# dual_seq_v1_0_0_main.net
KiCad netlist of a schematic drawn in EAGLE
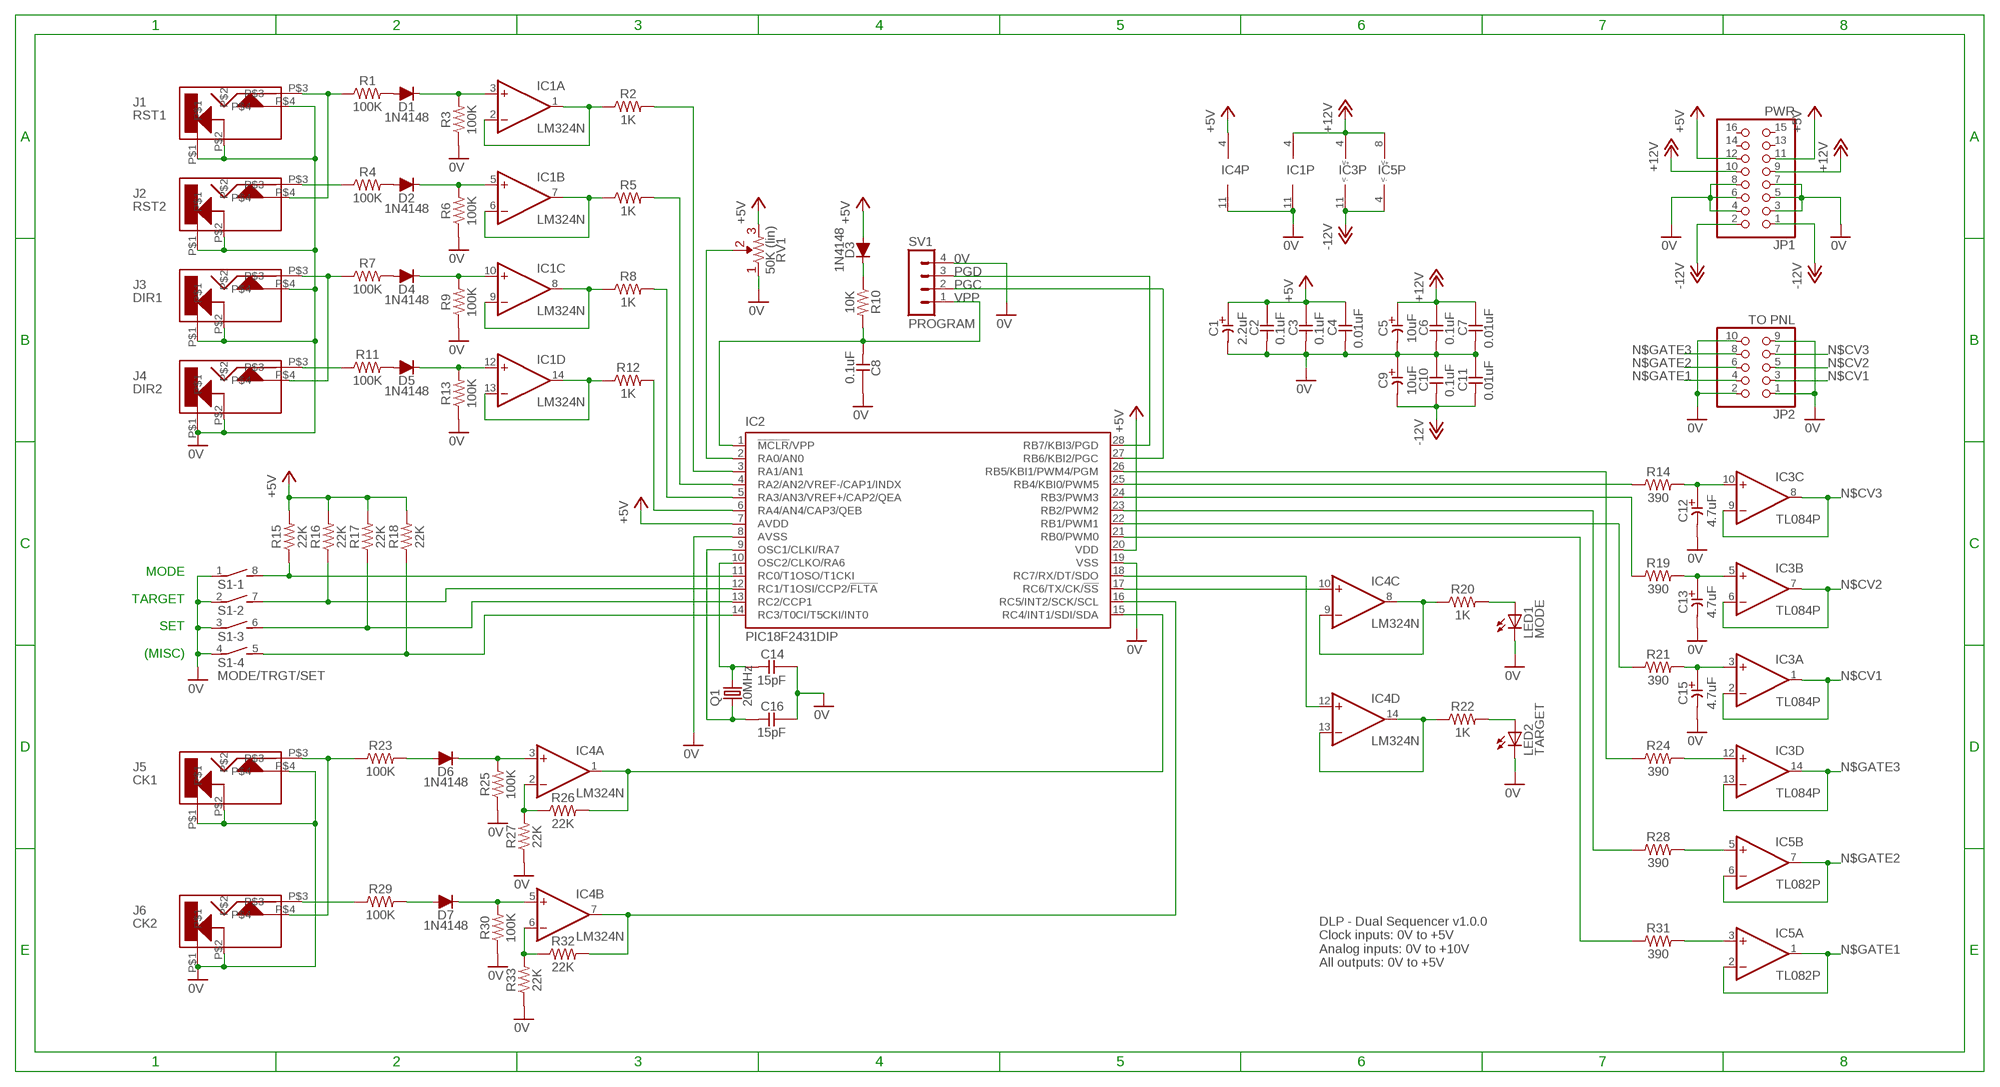
[diagram p0: schematic, sheet 1]

(export (version "E")
  (design (tool "Eeschema 10.0.6"))
  (components
    (comp (ref "C1")
      (value "2.2uF")
      (footprint "eagle-import:E2-5")
      (libsource (lib "eagle-import") (part "CE-USE2-5"))
    )
    (comp (ref "C2")
      (value "0.1uF")
      (footprint "eagle-import:C025-024X044")
      (libsource (lib "eagle-import") (part "CC-US025-024X044"))
    )
    (comp (ref "C3")
      (value "0.1uF")
      (footprint "eagle-import:C025-024X044")
      (libsource (lib "eagle-import") (part "CC-US025-024X044"))
    )
    (comp (ref "C4")
      (value "0.01uF")
      (footprint "eagle-import:C025-024X044")
      (libsource (lib "eagle-import") (part "CC-US025-024X044"))
    )
    (comp (ref "C5")
      (value "10uF")
      (footprint "eagle-import:E2-5")
      (libsource (lib "eagle-import") (part "CE-USE2-5"))
    )
    (comp (ref "C6")
      (value "0.1uF")
      (footprint "eagle-import:C025-024X044")
      (libsource (lib "eagle-import") (part "CC-US025-024X044"))
    )
    (comp (ref "C7")
      (value "0.01uF")
      (footprint "eagle-import:C025-024X044")
      (libsource (lib "eagle-import") (part "CC-US025-024X044"))
    )
    (comp (ref "C8")
      (value "0.1uF")
      (footprint "eagle-import:C025-024X044")
      (libsource (lib "eagle-import") (part "CC-US025-024X044"))
    )
    (comp (ref "C9")
      (value "10uF")
      (footprint "eagle-import:E2-5")
      (libsource (lib "eagle-import") (part "CE-USE2-5"))
    )
    (comp (ref "C10")
      (value "0.1uF")
      (footprint "eagle-import:C025-024X044")
      (libsource (lib "eagle-import") (part "CC-US025-024X044"))
    )
    (comp (ref "C11")
      (value "0.01uF")
      (footprint "eagle-import:C025-024X044")
      (libsource (lib "eagle-import") (part "CC-US025-024X044"))
    )
    (comp (ref "C12")
      (value "4.7uF")
      (footprint "eagle-import:E2-5")
      (libsource (lib "eagle-import") (part "CE-USE2-5"))
    )
    (comp (ref "C13")
      (value "4.7uF")
      (footprint "eagle-import:E2-5")
      (libsource (lib "eagle-import") (part "CE-USE2-5"))
    )
    (comp (ref "C14")
      (value "15pF")
      (footprint "eagle-import:C025-024X044")
      (libsource (lib "eagle-import") (part "CC-US025-024X044"))
    )
    (comp (ref "C15")
      (value "4.7uF")
      (footprint "eagle-import:E2-5")
      (libsource (lib "eagle-import") (part "CE-USE2-5"))
    )
    (comp (ref "C16")
      (value "15pF")
      (footprint "eagle-import:C025-024X044")
      (libsource (lib "eagle-import") (part "CC-US025-024X044"))
    )
    (comp (ref "D1")
      (value "1N4148")
      (footprint "eagle-import:DO34-5")
      (libsource (lib "eagle-import") (part "1N4148"))
    )
    (comp (ref "D2")
      (value "1N4148")
      (footprint "eagle-import:DO34-5")
      (libsource (lib "eagle-import") (part "1N4148"))
    )
    (comp (ref "D3")
      (value "1N4148")
      (footprint "eagle-import:DO34-5")
      (libsource (lib "eagle-import") (part "1N4148"))
    )
    (comp (ref "D4")
      (value "1N4148")
      (footprint "eagle-import:DO34-5")
      (libsource (lib "eagle-import") (part "1N4148"))
    )
    (comp (ref "D5")
      (value "1N4148")
      (footprint "eagle-import:DO34-5")
      (libsource (lib "eagle-import") (part "1N4148"))
    )
    (comp (ref "D6")
      (value "1N4148")
      (footprint "eagle-import:DO34-5")
      (libsource (lib "eagle-import") (part "1N4148"))
    )
    (comp (ref "D7")
      (value "1N4148")
      (footprint "eagle-import:DO34-5")
      (libsource (lib "eagle-import") (part "1N4148"))
    )
    (comp (ref "IC1")
      (value "LM324N")
      (footprint "eagle-import:DIL14")
      (libsource (lib "eagle-import") (part "LM324N"))
    )
    (comp (ref "IC2")
      (value "PIC18F2431DIP")
      (footprint "eagle-import:DIL28-3")
      (fields (field (name "MF") "MICROCHIP") (field (name "MPN") "PIC18F2431-I/SP"))
      (libsource (lib "eagle-import") (part "PIC18F231DIP4"))
    )
    (comp (ref "IC3")
      (value "TL084P")
      (footprint "eagle-import:DIL14")
      (libsource (lib "eagle-import") (part "TL084P"))
    )
    (comp (ref "IC4")
      (value "LM324N")
      (footprint "eagle-import:DIL14")
      (libsource (lib "eagle-import") (part "LM324N"))
    )
    (comp (ref "IC5")
      (value "TL082P")
      (footprint "eagle-import:DIL08")
      (libsource (lib "eagle-import") (part "TL082P"))
    )
    (comp (ref "J1")
      (value "RST1")
      (footprint "eagle-import:CL1384")
      (libsource (lib "eagle-import") (part "CL1384"))
    )
    (comp (ref "J2")
      (value "RST2")
      (footprint "eagle-import:CL1384")
      (libsource (lib "eagle-import") (part "CL1384"))
    )
    (comp (ref "J3")
      (value "DIR1")
      (footprint "eagle-import:CL1384")
      (libsource (lib "eagle-import") (part "CL1384"))
    )
    (comp (ref "J4")
      (value "DIR2")
      (footprint "eagle-import:CL1384")
      (libsource (lib "eagle-import") (part "CL1384"))
    )
    (comp (ref "J5")
      (value "CK1")
      (footprint "eagle-import:CL1384")
      (libsource (lib "eagle-import") (part "CL1384"))
    )
    (comp (ref "J6")
      (value "CK2")
      (footprint "eagle-import:CL1384")
      (libsource (lib "eagle-import") (part "CL1384"))
    )
    (comp (ref "JP1")
      (value "PWR")
      (footprint "eagle-import:2X08")
      (libsource (lib "eagle-import") (part "PINHD-2X8"))
    )
    (comp (ref "JP2")
      (value "TO PNL")
      (footprint "eagle-import:2X05")
      (libsource (lib "eagle-import") (part "PINHD-2X5"))
    )
    (comp (ref "LED1")
      (value "MODE")
      (footprint "eagle-import:LED3MM")
      (libsource (lib "eagle-import") (part "LED3MM"))
    )
    (comp (ref "LED2")
      (value "TARGET")
      (footprint "eagle-import:LED3MM")
      (libsource (lib "eagle-import") (part "LED3MM"))
    )
    (comp (ref "Q1")
      (value "20MHz")
      (footprint "eagle-import:HC49_S")
      (libsource (lib "eagle-import") (part "CRYSTALHC49S"))
    )
    (comp (ref "R1")
      (value "100K")
      (footprint "eagle-import:0207_7")
      (libsource (lib "eagle-import") (part "R"))
    )
    (comp (ref "R2")
      (value "1K")
      (footprint "eagle-import:0207_7")
      (libsource (lib "eagle-import") (part "R"))
    )
    (comp (ref "R3")
      (value "100K")
      (footprint "eagle-import:0207_7")
      (libsource (lib "eagle-import") (part "R"))
    )
    (comp (ref "R4")
      (value "100K")
      (footprint "eagle-import:0207_7")
      (libsource (lib "eagle-import") (part "R"))
    )
    (comp (ref "R5")
      (value "1K")
      (footprint "eagle-import:0207_7")
      (libsource (lib "eagle-import") (part "R"))
    )
    (comp (ref "R6")
      (value "100K")
      (footprint "eagle-import:0207_7")
      (libsource (lib "eagle-import") (part "R"))
    )
    (comp (ref "R7")
      (value "100K")
      (footprint "eagle-import:0207_7")
      (libsource (lib "eagle-import") (part "R"))
    )
    (comp (ref "R8")
      (value "1K")
      (footprint "eagle-import:0207_7")
      (libsource (lib "eagle-import") (part "R"))
    )
    (comp (ref "R9")
      (value "100K")
      (footprint "eagle-import:0207_7")
      (libsource (lib "eagle-import") (part "R"))
    )
    (comp (ref "R10")
      (value "10K")
      (footprint "eagle-import:0207_7")
      (libsource (lib "eagle-import") (part "R"))
    )
    (comp (ref "R11")
      (value "100K")
      (footprint "eagle-import:0207_7")
      (libsource (lib "eagle-import") (part "R"))
    )
    (comp (ref "R12")
      (value "1K")
      (footprint "eagle-import:0207_7")
      (libsource (lib "eagle-import") (part "R"))
    )
    (comp (ref "R13")
      (value "100K")
      (footprint "eagle-import:0207_7")
      (libsource (lib "eagle-import") (part "R"))
    )
    (comp (ref "R14")
      (value "390")
      (footprint "eagle-import:0207_7")
      (libsource (lib "eagle-import") (part "R"))
    )
    (comp (ref "R15")
      (value "22K")
      (footprint "eagle-import:0207_7")
      (libsource (lib "eagle-import") (part "R"))
    )
    (comp (ref "R16")
      (value "22K")
      (footprint "eagle-import:0207_7")
      (libsource (lib "eagle-import") (part "R"))
    )
    (comp (ref "R17")
      (value "22K")
      (footprint "eagle-import:0207_7")
      (libsource (lib "eagle-import") (part "R"))
    )
    (comp (ref "R18")
      (value "22K")
      (footprint "eagle-import:0207_7")
      (libsource (lib "eagle-import") (part "R"))
    )
    (comp (ref "R19")
      (value "390")
      (footprint "eagle-import:0207_7")
      (libsource (lib "eagle-import") (part "R"))
    )
    (comp (ref "R20")
      (value "1K")
      (footprint "eagle-import:0207_7")
      (libsource (lib "eagle-import") (part "R"))
    )
    (comp (ref "R21")
      (value "390")
      (footprint "eagle-import:0207_7")
      (libsource (lib "eagle-import") (part "R"))
    )
    (comp (ref "R22")
      (value "1K")
      (footprint "eagle-import:0207_7")
      (libsource (lib "eagle-import") (part "R"))
    )
    (comp (ref "R23")
      (value "100K")
      (footprint "eagle-import:0207_7")
      (libsource (lib "eagle-import") (part "R"))
    )
    (comp (ref "R24")
      (value "390")
      (footprint "eagle-import:0207_7")
      (libsource (lib "eagle-import") (part "R"))
    )
    (comp (ref "R25")
      (value "100K")
      (footprint "eagle-import:0207_7")
      (libsource (lib "eagle-import") (part "R"))
    )
    (comp (ref "R26")
      (value "22K")
      (footprint "eagle-import:0207_7")
      (libsource (lib "eagle-import") (part "R"))
    )
    (comp (ref "R27")
      (value "22K")
      (footprint "eagle-import:0207_7")
      (libsource (lib "eagle-import") (part "R"))
    )
    (comp (ref "R28")
      (value "390")
      (footprint "eagle-import:0207_7")
      (libsource (lib "eagle-import") (part "R"))
    )
    (comp (ref "R29")
      (value "100K")
      (footprint "eagle-import:0207_7")
      (libsource (lib "eagle-import") (part "R"))
    )
    (comp (ref "R30")
      (value "100K")
      (footprint "eagle-import:0207_7")
      (libsource (lib "eagle-import") (part "R"))
    )
    (comp (ref "R31")
      (value "390")
      (footprint "eagle-import:0207_7")
      (libsource (lib "eagle-import") (part "R"))
    )
    (comp (ref "R32")
      (value "22K")
      (footprint "eagle-import:0207_7")
      (libsource (lib "eagle-import") (part "R"))
    )
    (comp (ref "R33")
      (value "22K")
      (footprint "eagle-import:0207_7")
      (libsource (lib "eagle-import") (part "R"))
    )
    (comp (ref "RV1")
      (value "50K (lin)")
      (footprint "eagle-import:R-VAR")
      (libsource (lib "eagle-import") (part "R-VAR"))
    )
    (comp (ref "S1")
      (value "MODE/TRGT/SET")
      (footprint "eagle-import:DIP04S")
      (libsource (lib "eagle-import") (part "DIP04S"))
    )
    (comp (ref "SV1")
      (value "PROGRAM")
      (footprint "eagle-import:MA04-1")
      (libsource (lib "eagle-import") (part "MA04-1"))
    )
  )
  (nets
    (net (code "1") (name "+5V") (class "Default")
      (node (ref "C1") (pin "+") (pinfunction "+_+") (pintype "passive"))
      (node (ref "C2") (pin "1") (pinfunction "1_1") (pintype "passive"))
      (node (ref "C3") (pin "1") (pinfunction "1_1") (pintype "passive"))
      (node (ref "C4") (pin "1") (pinfunction "1_1") (pintype "passive"))
      (node (ref "D3") (pin "A") (pinfunction "A_A") (pintype "passive"))
      (node (ref "IC2") (pin "20") (pinfunction "VDD_20") (pintype "power_in"))
      (node (ref "IC2") (pin "7") (pinfunction "AVDD_7") (pintype "power_in"))
      (node (ref "IC4") (pin "4") (pinfunction "V+_4") (pintype "power_in"))
      (node (ref "JP1") (pin "11") (pinfunction "11_11") (pintype "passive"))
      (node (ref "JP1") (pin "12") (pinfunction "12_12") (pintype "passive"))
      (node (ref "R15") (pin "2") (pinfunction "2_2") (pintype "passive"))
      (node (ref "R16") (pin "2") (pinfunction "2_2") (pintype "passive"))
      (node (ref "R17") (pin "2") (pinfunction "2_2") (pintype "passive"))
      (node (ref "R18") (pin "2") (pinfunction "2_2") (pintype "passive"))
      (node (ref "RV1") (pin "R2") (pinfunction "2_R2") (pintype "passive"))
    )
    (net (code "2") (name "+12V") (class "Default")
      (node (ref "C5") (pin "+") (pinfunction "+_+") (pintype "passive"))
      (node (ref "C6") (pin "1") (pinfunction "1_1") (pintype "passive"))
      (node (ref "C7") (pin "1") (pinfunction "1_1") (pintype "passive"))
      (node (ref "IC1") (pin "4") (pinfunction "V+_4") (pintype "power_in"))
      (node (ref "IC3") (pin "4") (pinfunction "V+_4") (pintype "power_in"))
      (node (ref "IC5") (pin "8") (pinfunction "V+_8") (pintype "power_in"))
      (node (ref "JP1") (pin "10") (pinfunction "10_10") (pintype "passive"))
      (node (ref "JP1") (pin "9") (pinfunction "9_9") (pintype "passive"))
    )
    (net (code "3") (name "-12V") (class "Default")
      (node (ref "C10") (pin "2") (pinfunction "2_2") (pintype "passive"))
      (node (ref "C11") (pin "2") (pinfunction "2_2") (pintype "passive"))
      (node (ref "C9") (pin "-") (pinfunction "-_-") (pintype "passive"))
      (node (ref "IC3") (pin "11") (pinfunction "V-_11") (pintype "power_in"))
      (node (ref "IC5") (pin "4") (pinfunction "V-_4") (pintype "power_in"))
      (node (ref "JP1") (pin "1") (pinfunction "1_1") (pintype "passive"))
      (node (ref "JP1") (pin "2") (pinfunction "2_2") (pintype "passive"))
    )
    (net (code "4") (name "/N$CV1") (class "Default")
      (node (ref "IC3") (pin "1") (pinfunction "OUT_1") (pintype "output"))
      (node (ref "IC3") (pin "2") (pinfunction "-IN_2") (pintype "input"))
      (node (ref "JP2") (pin "3") (pinfunction "3_3") (pintype "passive"))
    )
    (net (code "5") (name "/N$CV2") (class "Default")
      (node (ref "IC3") (pin "6") (pinfunction "-IN_6") (pintype "input"))
      (node (ref "IC3") (pin "7") (pinfunction "OUT_7") (pintype "output"))
      (node (ref "JP2") (pin "5") (pinfunction "5_5") (pintype "passive"))
    )
    (net (code "6") (name "/N$CV3") (class "Default")
      (node (ref "IC3") (pin "8") (pinfunction "OUT_8") (pintype "output"))
      (node (ref "IC3") (pin "9") (pinfunction "-IN_9") (pintype "input"))
      (node (ref "JP2") (pin "7") (pinfunction "7_7") (pintype "passive"))
    )
    (net (code "7") (name "/N$GATE1") (class "Default")
      (node (ref "IC5") (pin "1") (pinfunction "OUT_1") (pintype "output"))
      (node (ref "IC5") (pin "2") (pinfunction "-IN_2") (pintype "input"))
      (node (ref "JP2") (pin "4") (pinfunction "4_4") (pintype "passive"))
    )
    (net (code "8") (name "/N$GATE2") (class "Default")
      (node (ref "IC5") (pin "6") (pinfunction "-IN_6") (pintype "input"))
      (node (ref "IC5") (pin "7") (pinfunction "OUT_7") (pintype "output"))
      (node (ref "JP2") (pin "6") (pinfunction "6_6") (pintype "passive"))
    )
    (net (code "9") (name "/N$GATE3") (class "Default")
      (node (ref "IC3") (pin "13") (pinfunction "-IN_13") (pintype "input"))
      (node (ref "IC3") (pin "14") (pinfunction "OUT_14") (pintype "output"))
      (node (ref "JP2") (pin "8") (pinfunction "8_8") (pintype "passive"))
    )
    (net (code "10") (name "/PGC") (class "Default")
      (node (ref "IC2") (pin "27") (pinfunction "RB6/KBI2/PGC_27") (pintype "bidirectional"))
      (node (ref "SV1") (pin "2") (pinfunction "2_2") (pintype "passive"))
    )
    (net (code "11") (name "/PGD") (class "Default")
      (node (ref "IC2") (pin "28") (pinfunction "RB7/KBI3/PGD_28") (pintype "bidirectional"))
      (node (ref "SV1") (pin "3") (pinfunction "3_3") (pintype "passive"))
    )
    (net (code "12") (name "/VPP") (class "Default")
      (node (ref "C8") (pin "2") (pinfunction "2_2") (pintype "passive"))
      (node (ref "IC2") (pin "1") (pinfunction "~{MCLR}/VPP_1") (pintype "input"))
      (node (ref "R10") (pin "2") (pinfunction "2_2") (pintype "passive"))
      (node (ref "SV1") (pin "1") (pinfunction "1_1") (pintype "passive"))
    )
    (net (code "13") (name "0V") (class "Default")
      (node (ref "C1") (pin "-") (pinfunction "-_-") (pintype "passive"))
      (node (ref "C10") (pin "1") (pinfunction "1_1") (pintype "passive"))
      (node (ref "C11") (pin "1") (pinfunction "1_1") (pintype "passive"))
      (node (ref "C12") (pin "-") (pinfunction "-_-") (pintype "passive"))
      (node (ref "C13") (pin "-") (pinfunction "-_-") (pintype "passive"))
      (node (ref "C14") (pin "1") (pinfunction "1_1") (pintype "passive"))
      (node (ref "C15") (pin "-") (pinfunction "-_-") (pintype "passive"))
      (node (ref "C16") (pin "1") (pinfunction "1_1") (pintype "passive"))
      (node (ref "C2") (pin "2") (pinfunction "2_2") (pintype "passive"))
      (node (ref "C3") (pin "2") (pinfunction "2_2") (pintype "passive"))
      (node (ref "C4") (pin "2") (pinfunction "2_2") (pintype "passive"))
      (node (ref "C5") (pin "-") (pinfunction "-_-") (pintype "passive"))
      (node (ref "C6") (pin "2") (pinfunction "2_2") (pintype "passive"))
      (node (ref "C7") (pin "2") (pinfunction "2_2") (pintype "passive"))
      (node (ref "C8") (pin "1") (pinfunction "1_1") (pintype "passive"))
      (node (ref "C9") (pin "+") (pinfunction "+_+") (pintype "passive"))
      (node (ref "IC1") (pin "11") (pinfunction "V-_11") (pintype "power_in"))
      (node (ref "IC2") (pin "19") (pinfunction "VSS_19") (pintype "power_in"))
      (node (ref "IC2") (pin "8") (pinfunction "AVSS_8") (pintype "power_in"))
      (node (ref "IC4") (pin "11") (pinfunction "V-_11") (pintype "power_in"))
      (node (ref "J1") (pin "P$1") (pinfunction "P$1_P$1") (pintype "bidirectional"))
      (node (ref "J1") (pin "P$2") (pinfunction "P$2_P$2") (pintype "bidirectional"))
      (node (ref "J1") (pin "P$4") (pinfunction "P$4_P$4") (pintype "bidirectional"))
      (node (ref "J2") (pin "P$1") (pinfunction "P$1_P$1") (pintype "bidirectional"))
      (node (ref "J2") (pin "P$2") (pinfunction "P$2_P$2") (pintype "bidirectional"))
      (node (ref "J3") (pin "P$1") (pinfunction "P$1_P$1") (pintype "bidirectional"))
      (node (ref "J3") (pin "P$2") (pinfunction "P$2_P$2") (pintype "bidirectional"))
      (node (ref "J3") (pin "P$4") (pinfunction "P$4_P$4") (pintype "bidirectional"))
      (node (ref "J4") (pin "P$1") (pinfunction "P$1_P$1") (pintype "bidirectional"))
      (node (ref "J4") (pin "P$2") (pinfunction "P$2_P$2") (pintype "bidirectional"))
      (node (ref "J5") (pin "P$1") (pinfunction "P$1_P$1") (pintype "bidirectional"))
      (node (ref "J5") (pin "P$2") (pinfunction "P$2_P$2") (pintype "bidirectional"))
      (node (ref "J5") (pin "P$4") (pinfunction "P$4_P$4") (pintype "bidirectional"))
      (node (ref "J6") (pin "P$1") (pinfunction "P$1_P$1") (pintype "bidirectional"))
      (node (ref "J6") (pin "P$2") (pinfunction "P$2_P$2") (pintype "bidirectional"))
      (node (ref "JP1") (pin "3") (pinfunction "3_3") (pintype "passive"))
      (node (ref "JP1") (pin "4") (pinfunction "4_4") (pintype "passive"))
      (node (ref "JP1") (pin "5") (pinfunction "5_5") (pintype "passive"))
      (node (ref "JP1") (pin "6") (pinfunction "6_6") (pintype "passive"))
      (node (ref "JP1") (pin "7") (pinfunction "7_7") (pintype "passive"))
      (node (ref "JP1") (pin "8") (pinfunction "8_8") (pintype "passive"))
      (node (ref "JP2") (pin "1") (pinfunction "1_1") (pintype "passive"))
      (node (ref "JP2") (pin "10") (pinfunction "10_10") (pintype "passive"))
      (node (ref "JP2") (pin "2") (pinfunction "2_2") (pintype "passive"))
      (node (ref "JP2") (pin "9") (pinfunction "9_9") (pintype "passive"))
      (node (ref "LED1") (pin "K") (pinfunction "C_K") (pintype "passive"))
      (node (ref "LED2") (pin "K") (pinfunction "C_K") (pintype "passive"))
      (node (ref "R13") (pin "1") (pinfunction "1_1") (pintype "passive"))
      (node (ref "R25") (pin "1") (pinfunction "1_1") (pintype "passive"))
      (node (ref "R27") (pin "1") (pinfunction "1_1") (pintype "passive"))
      (node (ref "R3") (pin "1") (pinfunction "1_1") (pintype "passive"))
      (node (ref "R30") (pin "1") (pinfunction "1_1") (pintype "passive"))
      (node (ref "R33") (pin "1") (pinfunction "1_1") (pintype "passive"))
      (node (ref "R6") (pin "1") (pinfunction "1_1") (pintype "passive"))
      (node (ref "R9") (pin "1") (pinfunction "1_1") (pintype "passive"))
      (node (ref "RV1") (pin "R1") (pinfunction "1_R1") (pintype "passive"))
      (node (ref "S1") (pin "1") (pinfunction "1_1") (pintype "passive"))
      (node (ref "S1") (pin "2") (pinfunction "1_2") (pintype "passive"))
      (node (ref "S1") (pin "3") (pinfunction "1_3") (pintype "passive"))
      (node (ref "S1") (pin "4") (pinfunction "1_4") (pintype "passive"))
      (node (ref "SV1") (pin "4") (pinfunction "4_4") (pintype "passive"))
    )
    (net (code "14") (name "Net-(D1-PadA)") (class "Default")
      (node (ref "D1") (pin "A") (pinfunction "A_A") (pintype "passive"))
      (node (ref "R1") (pin "2") (pinfunction "2_2") (pintype "passive"))
    )
    (net (code "15") (name "Net-(D2-PadA)") (class "Default")
      (node (ref "D2") (pin "A") (pinfunction "A_A") (pintype "passive"))
      (node (ref "R4") (pin "2") (pinfunction "2_2") (pintype "passive"))
    )
    (net (code "16") (name "Net-(D3-PadC)") (class "Default")
      (node (ref "D3") (pin "C") (pinfunction "C_C") (pintype "passive"))
      (node (ref "R10") (pin "1") (pinfunction "1_1") (pintype "passive"))
    )
    (net (code "17") (name "Net-(D4-PadA)") (class "Default")
      (node (ref "D4") (pin "A") (pinfunction "A_A") (pintype "passive"))
      (node (ref "R7") (pin "2") (pinfunction "2_2") (pintype "passive"))
    )
    (net (code "18") (name "Net-(D5-PadA)") (class "Default")
      (node (ref "D5") (pin "A") (pinfunction "A_A") (pintype "passive"))
      (node (ref "R11") (pin "2") (pinfunction "2_2") (pintype "passive"))
    )
    (net (code "19") (name "Net-(D6-PadA)") (class "Default")
      (node (ref "D6") (pin "A") (pinfunction "A_A") (pintype "passive"))
      (node (ref "R23") (pin "2") (pinfunction "2_2") (pintype "passive"))
    )
    (net (code "20") (name "Net-(D7-PadA)") (class "Default")
      (node (ref "D7") (pin "A") (pinfunction "A_A") (pintype "passive"))
      (node (ref "R29") (pin "2") (pinfunction "2_2") (pintype "passive"))
    )
    (net (code "21") (name "Net-(IC1A-+IN)") (class "Default")
      (node (ref "D1") (pin "C") (pinfunction "C_C") (pintype "passive"))
      (node (ref "IC1") (pin "3") (pinfunction "+IN_3") (pintype "input"))
      (node (ref "R3") (pin "2") (pinfunction "2_2") (pintype "passive"))
    )
    (net (code "22") (name "Net-(IC1A--IN)") (class "Default")
      (node (ref "IC1") (pin "1") (pinfunction "OUT_1") (pintype "output"))
      (node (ref "IC1") (pin "2") (pinfunction "-IN_2") (pintype "input"))
      (node (ref "R2") (pin "1") (pinfunction "1_1") (pintype "passive"))
    )
    (net (code "23") (name "Net-(IC1B-+IN)") (class "Default")
      (node (ref "D2") (pin "C") (pinfunction "C_C") (pintype "passive"))
      (node (ref "IC1") (pin "5") (pinfunction "+IN_5") (pintype "input"))
      (node (ref "R6") (pin "2") (pinfunction "2_2") (pintype "passive"))
    )
    (net (code "24") (name "Net-(IC1B--IN)") (class "Default")
      (node (ref "IC1") (pin "6") (pinfunction "-IN_6") (pintype "input"))
      (node (ref "IC1") (pin "7") (pinfunction "OUT_7") (pintype "output"))
      (node (ref "R5") (pin "1") (pinfunction "1_1") (pintype "passive"))
    )
    (net (code "25") (name "Net-(IC1C-+IN)") (class "Default")
      (node (ref "D4") (pin "C") (pinfunction "C_C") (pintype "passive"))
      (node (ref "IC1") (pin "10") (pinfunction "+IN_10") (pintype "input"))
      (node (ref "R9") (pin "2") (pinfunction "2_2") (pintype "passive"))
    )
    (net (code "26") (name "Net-(IC1C--IN)") (class "Default")
      (node (ref "IC1") (pin "8") (pinfunction "OUT_8") (pintype "output"))
      (node (ref "IC1") (pin "9") (pinfunction "-IN_9") (pintype "input"))
      (node (ref "R8") (pin "1") (pinfunction "1_1") (pintype "passive"))
    )
    (net (code "27") (name "Net-(IC1D-+IN)") (class "Default")
      (node (ref "D5") (pin "C") (pinfunction "C_C") (pintype "passive"))
      (node (ref "IC1") (pin "12") (pinfunction "+IN_12") (pintype "input"))
      (node (ref "R13") (pin "2") (pinfunction "2_2") (pintype "passive"))
    )
    (net (code "28") (name "Net-(IC1D--IN)") (class "Default")
      (node (ref "IC1") (pin "13") (pinfunction "-IN_13") (pintype "input"))
      (node (ref "IC1") (pin "14") (pinfunction "OUT_14") (pintype "output"))
      (node (ref "R12") (pin "1") (pinfunction "1_1") (pintype "passive"))
    )
    (net (code "29") (name "Net-(IC2-OSC1{slash}CLKI{slash}RA7)") (class "Default")
      (node (ref "C16") (pin "2") (pinfunction "2_2") (pintype "passive"))
      (node (ref "IC2") (pin "9") (pinfunction "OSC1/CLKI/RA7_9") (pintype "input"))
      (node (ref "Q1") (pin "1") (pinfunction "1_1") (pintype "passive"))
    )
    (net (code "30") (name "Net-(IC2-OSC2{slash}CLKO{slash}RA6)") (class "Default")
      (node (ref "C14") (pin "2") (pinfunction "2_2") (pintype "passive"))
      (node (ref "IC2") (pin "10") (pinfunction "OSC2/CLKO/RA6_10") (pintype "output"))
      (node (ref "Q1") (pin "2") (pinfunction "2_2") (pintype "passive"))
    )
    (net (code "31") (name "Net-(IC2-RA0{slash}AN0)") (class "Default")
      (node (ref "IC2") (pin "2") (pinfunction "RA0/AN0_2") (pintype "bidirectional"))
      (node (ref "RV1") (pin "VAR") (pinfunction "P$1_VAR") (pintype "passive"))
    )
    (net (code "32") (name "Net-(IC2-RA1{slash}AN1)") (class "Default")
      (node (ref "IC2") (pin "3") (pinfunction "RA1/AN1_3") (pintype "bidirectional"))
      (node (ref "R2") (pin "2") (pinfunction "2_2") (pintype "passive"))
    )
    (net (code "33") (name "Net-(IC2-RA2{slash}AN2{slash}VREF-{slash}CAP1{slash}INDX)") (class "Default")
      (node (ref "IC2") (pin "4") (pinfunction "RA2/AN2/VREF-/CAP1/INDX_4") (pintype "bidirectional"))
      (node (ref "R5") (pin "2") (pinfunction "2_2") (pintype "passive"))
    )
    (net (code "34") (name "Net-(IC2-RA3{slash}AN3{slash}VREF+{slash}CAP2{slash}QEA)") (class "Default")
      (node (ref "IC2") (pin "5") (pinfunction "RA3/AN3/VREF+/CAP2/QEA_5") (pintype "bidirectional"))
      (node (ref "R8") (pin "2") (pinfunction "2_2") (pintype "passive"))
    )
    (net (code "35") (name "Net-(IC2-RA4{slash}AN4{slash}CAP3{slash}QEB)") (class "Default")
      (node (ref "IC2") (pin "6") (pinfunction "RA4/AN4/CAP3/QEB_6") (pintype "bidirectional"))
      (node (ref "R12") (pin "2") (pinfunction "2_2") (pintype "passive"))
    )
    (net (code "36") (name "Net-(IC2-RB0{slash}PWM0)") (class "Default")
      (node (ref "IC2") (pin "21") (pinfunction "RB0/PWM0_21") (pintype "bidirectional"))
      (node (ref "R31") (pin "1") (pinfunction "1_1") (pintype "passive"))
    )
    (net (code "37") (name "Net-(IC2-RB1{slash}PWM1)") (class "Default")
      (node (ref "IC2") (pin "22") (pinfunction "RB1/PWM1_22") (pintype "bidirectional"))
      (node (ref "R21") (pin "1") (pinfunction "1_1") (pintype "passive"))
    )
    (net (code "38") (name "Net-(IC2-RB2{slash}PWM2)") (class "Default")
      (node (ref "IC2") (pin "23") (pinfunction "RB2/PWM2_23") (pintype "bidirectional"))
      (node (ref "R28") (pin "1") (pinfunction "1_1") (pintype "passive"))
    )
    (net (code "39") (name "Net-(IC2-RB3{slash}PWM3)") (class "Default")
      (node (ref "IC2") (pin "24") (pinfunction "RB3/PWM3_24") (pintype "bidirectional"))
      (node (ref "R19") (pin "1") (pinfunction "1_1") (pintype "passive"))
    )
    (net (code "40") (name "Net-(IC2-RB4{slash}KBI0{slash}PWM5)") (class "Default")
      (node (ref "IC2") (pin "25") (pinfunction "RB4/KBI0/PWM5_25") (pintype "bidirectional"))
      (node (ref "R14") (pin "1") (pinfunction "1_1") (pintype "passive"))
    )
    (net (code "41") (name "Net-(IC2-RB5{slash}KBI1{slash}PWM4{slash}PGM)") (class "Default")
      (node (ref "IC2") (pin "26") (pinfunction "RB5/KBI1/PWM4/PGM_26") (pintype "bidirectional"))
      (node (ref "R24") (pin "1") (pinfunction "1_1") (pintype "passive"))
    )
    (net (code "42") (name "Net-(IC2-RC0{slash}T1OSO{slash}T1CKI)") (class "Default")
      (node (ref "IC2") (pin "11") (pinfunction "RC0/T1OSO/T1CKI_11") (pintype "bidirectional"))
      (node (ref "R15") (pin "1") (pinfunction "1_1") (pintype "passive"))
      (node (ref "S1") (pin "8") (pinfunction "2_8") (pintype "passive"))
    )
    (net (code "43") (name "Net-(IC2-RC1{slash}T1OSI{slash}CCP2{slash}~{FLTA})") (class "Default")
      (node (ref "IC2") (pin "12") (pinfunction "RC1/T1OSI/CCP2/~{FLTA}_12") (pintype "bidirectional"))
      (node (ref "R16") (pin "1") (pinfunction "1_1") (pintype "passive"))
      (node (ref "S1") (pin "7") (pinfunction "2_7") (pintype "passive"))
    )
    (net (code "44") (name "Net-(IC2-RC2{slash}CCP1)") (class "Default")
      (node (ref "IC2") (pin "13") (pinfunction "RC2/CCP1_13") (pintype "bidirectional"))
      (node (ref "R17") (pin "1") (pinfunction "1_1") (pintype "passive"))
      (node (ref "S1") (pin "6") (pinfunction "2_6") (pintype "passive"))
    )
    (net (code "45") (name "Net-(IC2-RC3{slash}T0CI{slash}T5CKI{slash}INT0)") (class "Default")
      (node (ref "IC2") (pin "14") (pinfunction "RC3/T0CI/T5CKI/INT0_14") (pintype "bidirectional"))
      (node (ref "R18") (pin "1") (pinfunction "1_1") (pintype "passive"))
      (node (ref "S1") (pin "5") (pinfunction "2_5") (pintype "passive"))
    )
    (net (code "46") (name "Net-(IC2-RC4{slash}INT1{slash}SDI{slash}SDA)") (class "Default")
      (node (ref "IC2") (pin "15") (pinfunction "RC4/INT1/SDI/SDA_15") (pintype "bidirectional"))
      (node (ref "IC4") (pin "1") (pinfunction "OUT_1") (pintype "output"))
      (node (ref "R26") (pin "2") (pinfunction "2_2") (pintype "passive"))
    )
    (net (code "47") (name "Net-(IC2-RC5{slash}INT2{slash}SCK{slash}SCL)") (class "Default")
      (node (ref "IC2") (pin "16") (pinfunction "RC5/INT2/SCK/SCL_16") (pintype "bidirectional"))
      (node (ref "IC4") (pin "7") (pinfunction "OUT_7") (pintype "output"))
      (node (ref "R32") (pin "2") (pinfunction "2_2") (pintype "passive"))
    )
    (net (code "48") (name "Net-(IC2-RC6{slash}TX{slash}CK{slash}~{SS})") (class "Default")
      (node (ref "IC2") (pin "17") (pinfunction "RC6/TX/CK/~{SS}_17") (pintype "bidirectional"))
      (node (ref "IC4") (pin "10") (pinfunction "+IN_10") (pintype "input"))
    )
    (net (code "49") (name "Net-(IC2-RC7{slash}RX{slash}DT{slash}SDO)") (class "Default")
      (node (ref "IC2") (pin "18") (pinfunction "RC7/RX/DT/SDO_18") (pintype "bidirectional"))
      (node (ref "IC4") (pin "12") (pinfunction "+IN_12") (pintype "input"))
    )
    (net (code "50") (name "Net-(IC3A-+IN)") (class "Default")
      (node (ref "C15") (pin "+") (pinfunction "+_+") (pintype "passive"))
      (node (ref "IC3") (pin "3") (pinfunction "+IN_3") (pintype "input"))
      (node (ref "R21") (pin "2") (pinfunction "2_2") (pintype "passive"))
    )
    (net (code "51") (name "Net-(IC3B-+IN)") (class "Default")
      (node (ref "C13") (pin "+") (pinfunction "+_+") (pintype "passive"))
      (node (ref "IC3") (pin "5") (pinfunction "+IN_5") (pintype "input"))
      (node (ref "R19") (pin "2") (pinfunction "2_2") (pintype "passive"))
    )
    (net (code "52") (name "Net-(IC3C-+IN)") (class "Default")
      (node (ref "C12") (pin "+") (pinfunction "+_+") (pintype "passive"))
      (node (ref "IC3") (pin "10") (pinfunction "+IN_10") (pintype "input"))
      (node (ref "R14") (pin "2") (pinfunction "2_2") (pintype "passive"))
    )
    (net (code "53") (name "Net-(IC3D-+IN)") (class "Default")
      (node (ref "IC3") (pin "12") (pinfunction "+IN_12") (pintype "input"))
      (node (ref "R24") (pin "2") (pinfunction "2_2") (pintype "passive"))
    )
    (net (code "54") (name "Net-(IC4A-+IN)") (class "Default")
      (node (ref "D6") (pin "C") (pinfunction "C_C") (pintype "passive"))
      (node (ref "IC4") (pin "3") (pinfunction "+IN_3") (pintype "input"))
      (node (ref "R25") (pin "2") (pinfunction "2_2") (pintype "passive"))
    )
    (net (code "55") (name "Net-(IC4A--IN)") (class "Default")
      (node (ref "IC4") (pin "2") (pinfunction "-IN_2") (pintype "input"))
      (node (ref "R26") (pin "1") (pinfunction "1_1") (pintype "passive"))
      (node (ref "R27") (pin "2") (pinfunction "2_2") (pintype "passive"))
    )
    (net (code "56") (name "Net-(IC4B-+IN)") (class "Default")
      (node (ref "D7") (pin "C") (pinfunction "C_C") (pintype "passive"))
      (node (ref "IC4") (pin "5") (pinfunction "+IN_5") (pintype "input"))
      (node (ref "R30") (pin "2") (pinfunction "2_2") (pintype "passive"))
    )
    (net (code "57") (name "Net-(IC4B--IN)") (class "Default")
      (node (ref "IC4") (pin "6") (pinfunction "-IN_6") (pintype "input"))
      (node (ref "R32") (pin "1") (pinfunction "1_1") (pintype "passive"))
      (node (ref "R33") (pin "2") (pinfunction "2_2") (pintype "passive"))
    )
    (net (code "58") (name "Net-(IC4C--IN)") (class "Default")
      (node (ref "IC4") (pin "8") (pinfunction "OUT_8") (pintype "output"))
      (node (ref "IC4") (pin "9") (pinfunction "-IN_9") (pintype "input"))
      (node (ref "R20") (pin "1") (pinfunction "1_1") (pintype "passive"))
    )
    (net (code "59") (name "Net-(IC4D--IN)") (class "Default")
      (node (ref "IC4") (pin "13") (pinfunction "-IN_13") (pintype "input"))
      (node (ref "IC4") (pin "14") (pinfunction "OUT_14") (pintype "output"))
      (node (ref "R22") (pin "1") (pinfunction "1_1") (pintype "passive"))
    )
    (net (code "60") (name "Net-(IC5A-+IN)") (class "Default")
      (node (ref "IC5") (pin "3") (pinfunction "+IN_3") (pintype "input"))
      (node (ref "R31") (pin "2") (pinfunction "2_2") (pintype "passive"))
    )
    (net (code "61") (name "Net-(IC5B-+IN)") (class "Default")
      (node (ref "IC5") (pin "5") (pinfunction "+IN_5") (pintype "input"))
      (node (ref "R28") (pin "2") (pinfunction "2_2") (pintype "passive"))
    )
    (net (code "62") (name "Net-(J1-PadP$3)") (class "Default")
      (node (ref "J1") (pin "P$3") (pinfunction "P$3_P$3") (pintype "bidirectional"))
      (node (ref "J2") (pin "P$4") (pinfunction "P$4_P$4") (pintype "bidirectional"))
      (node (ref "R1") (pin "1") (pinfunction "1_1") (pintype "passive"))
    )
    (net (code "63") (name "Net-(J2-PadP$3)") (class "Default")
      (node (ref "J2") (pin "P$3") (pinfunction "P$3_P$3") (pintype "bidirectional"))
      (node (ref "R4") (pin "1") (pinfunction "1_1") (pintype "passive"))
    )
    (net (code "64") (name "Net-(J3-PadP$3)") (class "Default")
      (node (ref "J3") (pin "P$3") (pinfunction "P$3_P$3") (pintype "bidirectional"))
      (node (ref "J4") (pin "P$4") (pinfunction "P$4_P$4") (pintype "bidirectional"))
      (node (ref "R7") (pin "1") (pinfunction "1_1") (pintype "passive"))
    )
    (net (code "65") (name "Net-(J4-PadP$3)") (class "Default")
      (node (ref "J4") (pin "P$3") (pinfunction "P$3_P$3") (pintype "bidirectional"))
      (node (ref "R11") (pin "1") (pinfunction "1_1") (pintype "passive"))
    )
    (net (code "66") (name "Net-(J5-PadP$3)") (class "Default")
      (node (ref "J5") (pin "P$3") (pinfunction "P$3_P$3") (pintype "bidirectional"))
      (node (ref "J6") (pin "P$4") (pinfunction "P$4_P$4") (pintype "bidirectional"))
      (node (ref "R23") (pin "1") (pinfunction "1_1") (pintype "passive"))
    )
    (net (code "67") (name "Net-(J6-PadP$3)") (class "Default")
      (node (ref "J6") (pin "P$3") (pinfunction "P$3_P$3") (pintype "bidirectional"))
      (node (ref "R29") (pin "1") (pinfunction "1_1") (pintype "passive"))
    )
    (net (code "68") (name "Net-(LED1-PadA)") (class "Default")
      (node (ref "LED1") (pin "A") (pinfunction "A_A") (pintype "passive"))
      (node (ref "R20") (pin "2") (pinfunction "2_2") (pintype "passive"))
    )
    (net (code "69") (name "Net-(LED2-PadA)") (class "Default")
      (node (ref "LED2") (pin "A") (pinfunction "A_A") (pintype "passive"))
      (node (ref "R22") (pin "2") (pinfunction "2_2") (pintype "passive"))
    )
    (net (code "70") (name "unconnected-(JP1-Pad13)") (class "Default")
      (node (ref "JP1") (pin "13") (pinfunction "13_13") (pintype "passive"))
    )
    (net (code "71") (name "unconnected-(JP1-Pad14)") (class "Default")
      (node (ref "JP1") (pin "14") (pinfunction "14_14") (pintype "passive"))
    )
    (net (code "72") (name "unconnected-(JP1-Pad15)") (class "Default")
      (node (ref "JP1") (pin "15") (pinfunction "15_15") (pintype "passive"))
    )
    (net (code "73") (name "unconnected-(JP1-Pad16)") (class "Default")
      (node (ref "JP1") (pin "16") (pinfunction "16_16") (pintype "passive"))
    )
  )
)
